# SCH_WasserQualliSensor_V1_1_2022-12-06.net
KiCad netlist of a schematic drawn in EasyEDA
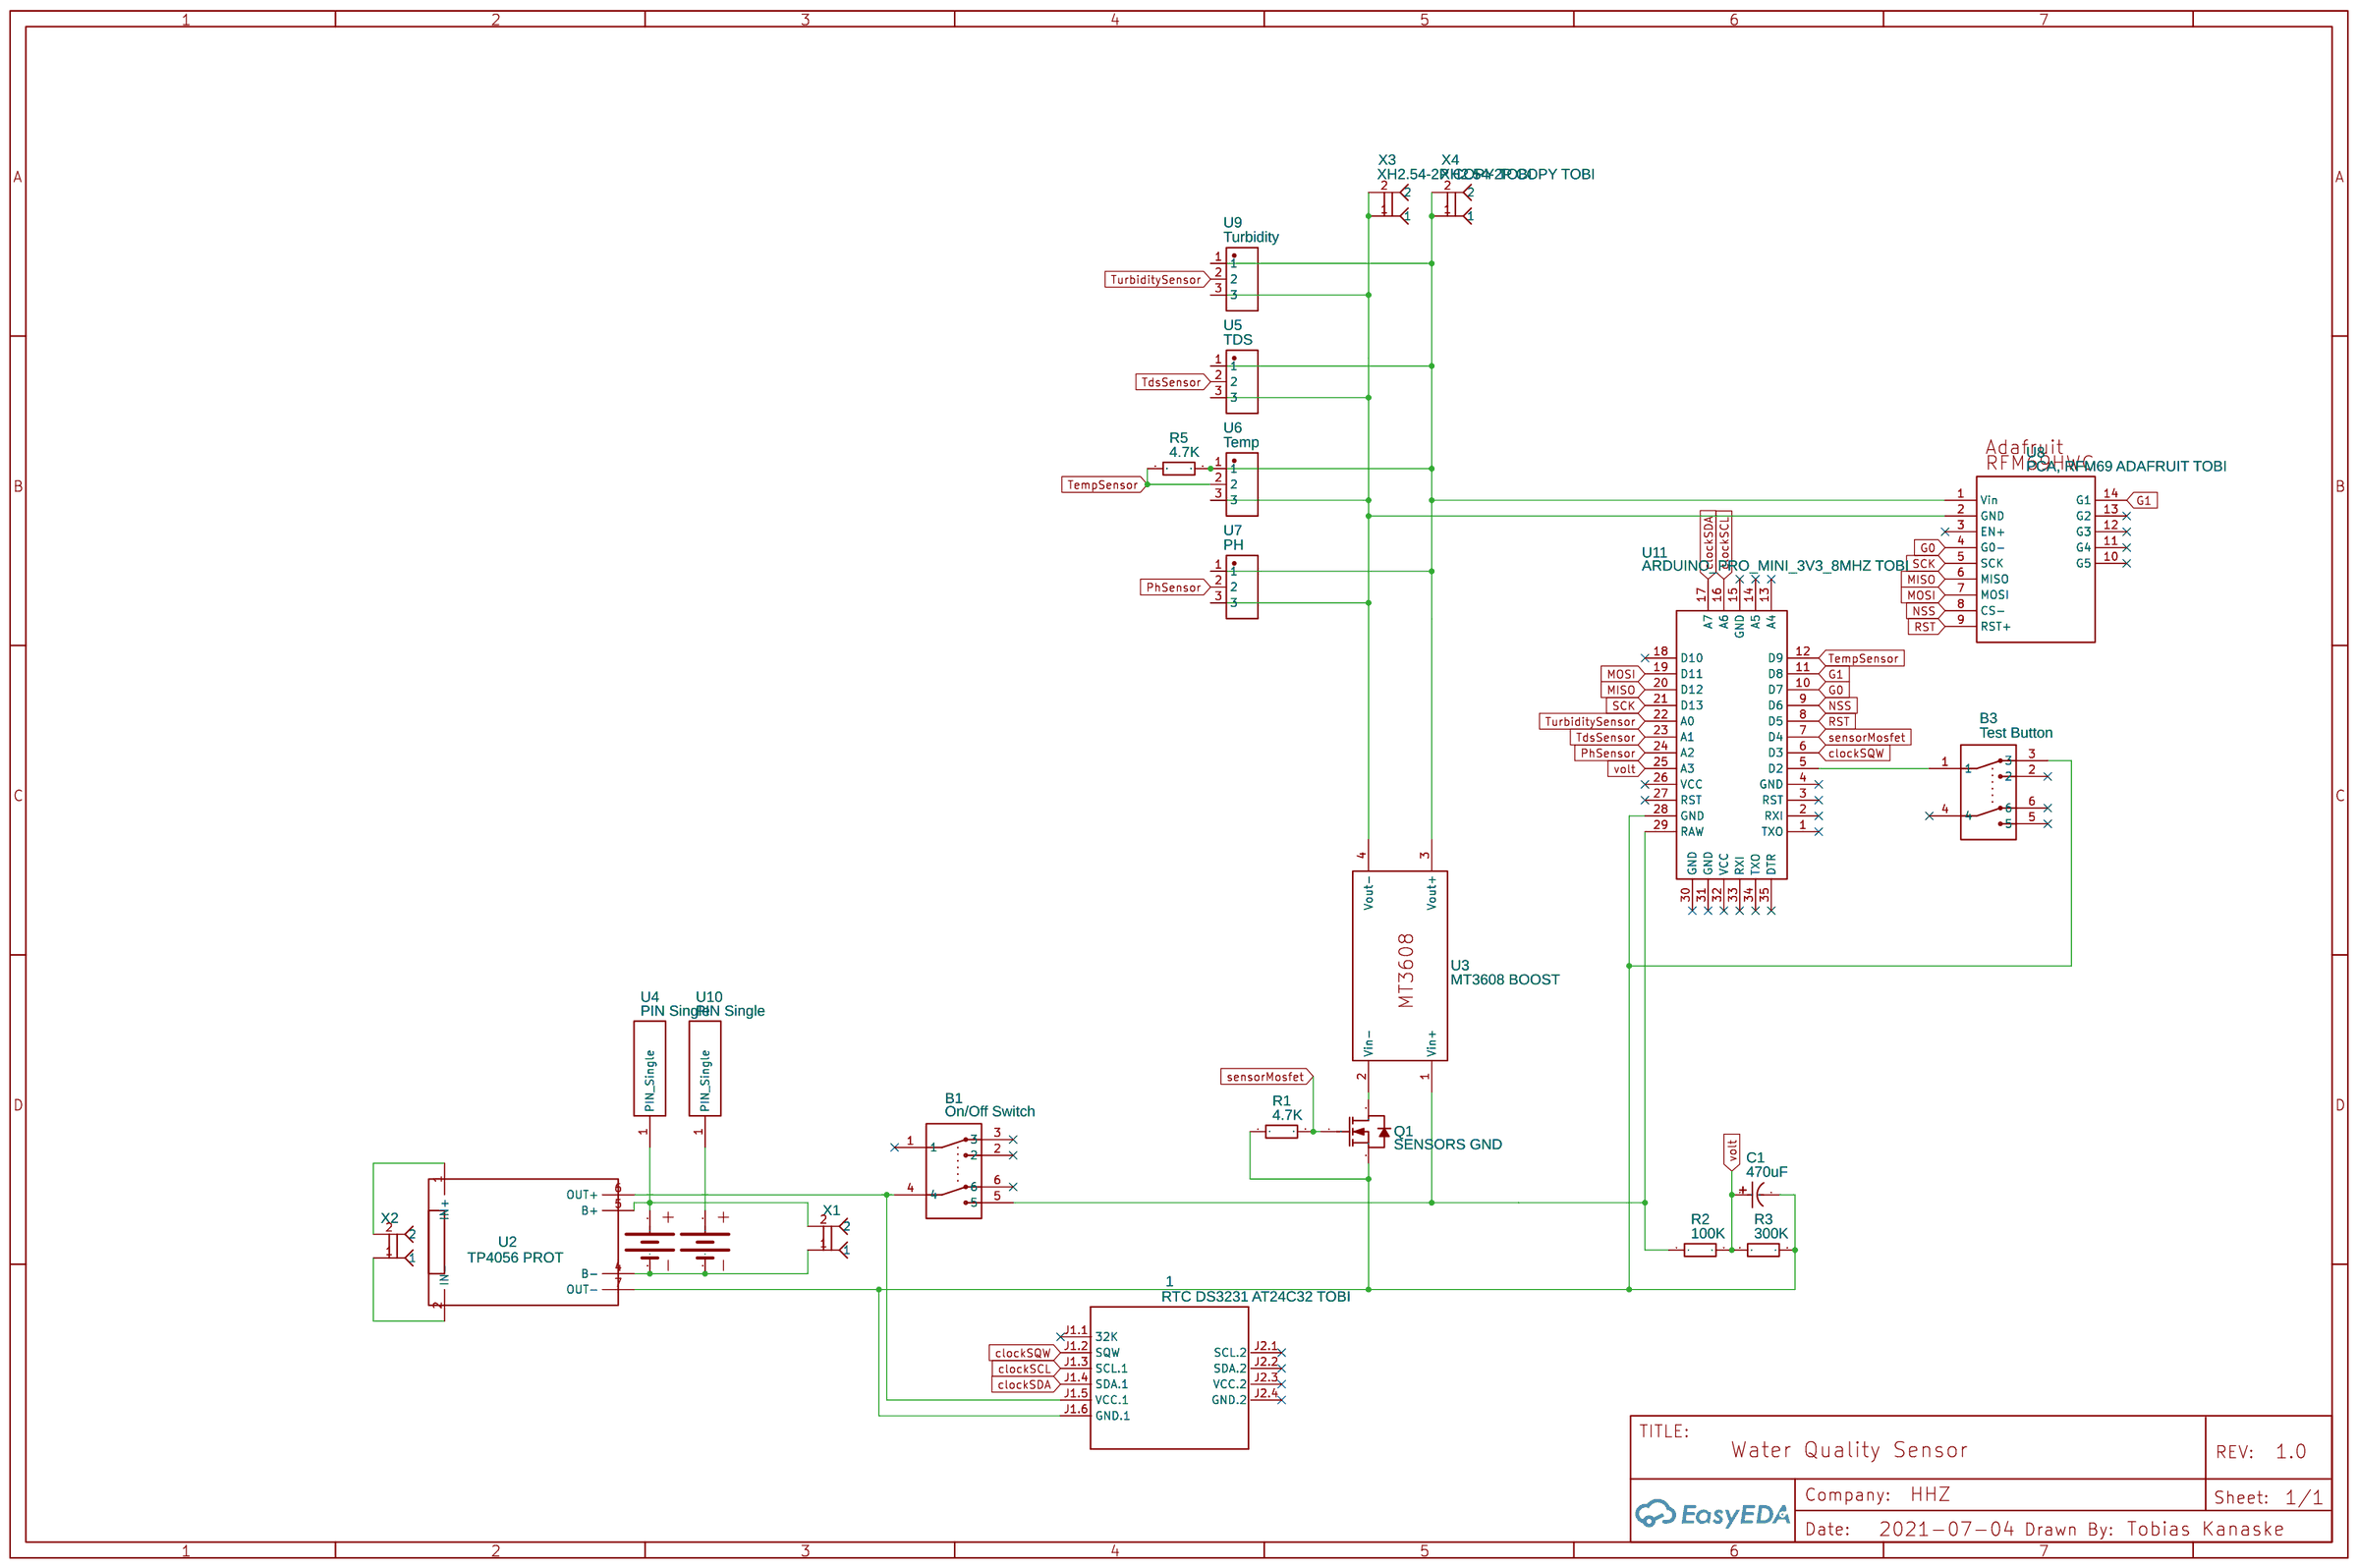
[diagram p0: schematic sheet]

(export (version "E")
  (design (tool "Eeschema 10.0.6"))
  (components
    (comp (ref "1") (value "RTC DS3231 AT24C32 TOBI") (libsource (lib "") (part "RTC DS3231 AT24C32 TOBI")))
    (comp (ref "3.1V") (value "18650") (libsource (lib "") (part "18650 SMD HOLDER 1S")))
    (comp (ref "4.2V") (value "18650") (libsource (lib "") (part "18650 SMD HOLDER 1S_1")))
    (comp (ref "B1")
      (value "On/Off Switch")
      (libsource (lib "") (part "LATCHING SWITCH BUTTON 8*8 6 PIN TOBI"))
    )
    (comp (ref "B3")
      (value "Test Button")
      (libsource (lib "") (part "LATCHING SWITCH BUTTON 8*8 6 PIN TOBI"))
    )
    (comp (ref "C1")
      (value "470uF")
      (fields
        (field (name "BOM_Manufacturer Part") "470uF 16V 6.3*12")
        (field (name "BOM_Supplier Part") "C43809")
      )
      (libsource (lib "") (part "KAPACITOR 470UF 16V 6.3*12 TOBI"))
    )
    (comp (ref "Q1")
      (value "SENSORS GND")
      (fields (field (name "BOM_Manufacturer Part") "IRLZ44NPBF") (field (name "BOM_Supplier Part") "C38774"))
      (libsource (lib "") (part "NPN MOSFET IRLZ44NPBF TOBI"))
    )
    (comp (ref "R1")
      (value "4.7K")
      (fields (field (name "BOM_Supplier Part") "C119339"))
      (libsource (lib "") (part "RESISTOR TOBI_1"))
    )
    (comp (ref "R2")
      (value "100K")
      (fields (field (name "BOM_Supplier Part") "C119339"))
      (libsource (lib "") (part "RESISTOR TOBI_1"))
    )
    (comp (ref "R3")
      (value "300K")
      (fields (field (name "BOM_Supplier Part") "C119339"))
      (libsource (lib "") (part "RESISTOR TOBI_1"))
    )
    (comp (ref "R5")
      (value "4.7K")
      (fields (field (name "BOM_Supplier Part") "C119339"))
      (libsource (lib "") (part "RESISTOR TOBI"))
    )
    (comp (ref "U2")
      (value "TP4056 PROT")
      (fields (field (name "BOM_Manufacturer Part") "TP4056-protect"))
      (libsource (lib "") (part "TP4056 PROT TOBI"))
    )
    (comp (ref "U3") (value "MT3608 BOOST") (libsource (lib "") (part "MT3608 BOOST TOBI")))
    (comp (ref "U4") (value "PIN Single") (libsource (lib "") (part "PIN Single")))
    (comp (ref "U5")
      (value "TDS")
      (fields
        (field (name "BOM_Manufacturer Part") "XH_2.54_3P")
        (field (name "BOM_Supplier Part") "C9900004241")
      )
      (libsource (lib "") (part "XH_2.54_3P TOBI"))
    )
    (comp (ref "U6")
      (value "Temp")
      (fields
        (field (name "BOM_Manufacturer Part") "XH_2.54_3P")
        (field (name "BOM_Supplier Part") "C9900004241")
      )
      (libsource (lib "") (part "XH_2.54_3P TOBI"))
    )
    (comp (ref "U7")
      (value "PH")
      (fields
        (field (name "BOM_Manufacturer Part") "XH_2.54_3P")
        (field (name "BOM_Supplier Part") "C9900004241")
      )
      (libsource (lib "") (part "XH_2.54_3P TOBI"))
    )
    (comp (ref "U8")
      (value "PCA, RFM69 ADAFRUIT TOBI")
      (fields (field (name "BOM_Manufacturer Part") "RFM69HCW") (field (name "BOM_Supplier Part") "C4746"))
      (libsource (lib "") (part "PCA, RFM69 ADAFRUIT TOBI"))
    )
    (comp (ref "U9")
      (value "Turbidity")
      (fields
        (field (name "BOM_Manufacturer Part") "XH_2.54_3P")
        (field (name "BOM_Supplier Part") "C9900004241")
      )
      (libsource (lib "") (part "XH_2.54_3P TOBI"))
    )
    (comp (ref "U10") (value "PIN Single") (libsource (lib "") (part "PIN Single")))
    (comp (ref "U11")
      (value "ARDUINO_PRO_MINI_3V3_8MHZ TOBI")
      (fields (field (name "BOM_Manufacturer Part") "Arduino_Pro_Mini_3V3_8Mhz"))
      (libsource (lib "") (part "ARDUINO_PRO_MINI_3V3_8MHZ TOBI"))
    )
    (comp (ref "X1") (value "XH2.54-2P") (libsource (lib "") (part "XH2.54-2P COPY TOBI")))
    (comp (ref "X2") (value "XH2.54-2P") (libsource (lib "") (part "XH2.54-2P COPY TOBI")))
    (comp (ref "X3")
      (value "XH2.54-2P COPY TOBI")
      (fields (field (name "BOM_Manufacturer Part") "XH2.54-2P"))
      (libsource (lib "") (part "XH2.54-2P COPY TOBI"))
    )
    (comp (ref "X4")
      (value "XH2.54-2P COPY TOBI")
      (fields (field (name "BOM_Manufacturer Part") "XH2.54-2P"))
      (libsource (lib "") (part "XH2.54-2P COPY TOBI"))
    )
  )
  (nets
    (net (code "1") (name "G0") (class "Default")
      (node (ref "U11") (pin "10") (pinfunction "D7_10") (pintype "unspecified"))
      (node (ref "U8") (pin "4") (pinfunction "G0-_4") (pintype "unspecified"))
    )
    (net (code "2") (name "G1") (class "Default")
      (node (ref "U11") (pin "11") (pinfunction "D8_11") (pintype "unspecified"))
      (node (ref "U8") (pin "14") (pinfunction "G1_14") (pintype "unspecified"))
    )
    (net (code "3") (name "MISO") (class "Default")
      (node (ref "U11") (pin "20") (pinfunction "D12_20") (pintype "unspecified"))
      (node (ref "U8") (pin "6") (pinfunction "MISO_6") (pintype "unspecified"))
    )
    (net (code "4") (name "MOSI") (class "Default")
      (node (ref "U11") (pin "19") (pinfunction "D11_19") (pintype "unspecified"))
      (node (ref "U8") (pin "7") (pinfunction "MOSI_7") (pintype "unspecified"))
    )
    (net (code "5") (name "NSS") (class "Default")
      (node (ref "U11") (pin "9") (pinfunction "D6_9") (pintype "unspecified"))
      (node (ref "U8") (pin "8") (pinfunction "CS-_8") (pintype "unspecified"))
    )
    (net (code "6") (name "Net-(1-GND.1)") (class "Default")
      (node (ref "1") (pin "J1.6") (pinfunction "GND.1_J1.6") (pintype "bidirectional"))
      (node (ref "B3") (pin "3") (pinfunction "3_3") (pintype "unspecified"))
      (node (ref "C1") (pin "2") (pinfunction "2_2") (pintype "input"))
      (node (ref "Q1") (pin "3") (pinfunction "S_3") (pintype "unspecified"))
      (node (ref "R1") (pin "1") (pinfunction "1_1") (pintype "unspecified"))
      (node (ref "R3") (pin "2") (pinfunction "2_2") (pintype "unspecified"))
      (node (ref "U11") (pin "28") (pinfunction "GND_28") (pintype "unspecified"))
      (node (ref "U2") (pin "7") (pinfunction "OUT-_7") (pintype "unspecified"))
    )
    (net (code "7") (name "Net-(1-VCC.1)") (class "Default")
      (node (ref "1") (pin "J1.5") (pinfunction "VCC.1_J1.5") (pintype "bidirectional"))
      (node (ref "B1") (pin "4") (pinfunction "4_4") (pintype "unspecified"))
      (node (ref "U2") (pin "6") (pinfunction "OUT+_6") (pintype "unspecified"))
    )
    (net (code "8") (name "Net-(3.1V-+)") (class "Default")
      (node (ref "3.1V") (pin "1") (pinfunction "+_1") (pintype "passive"))
      (node (ref "U10") (pin "1") (pinfunction "PIN_Single_1") (pintype "unspecified"))
    )
    (net (code "9") (name "Net-(3.1V--)") (class "Default")
      (node (ref "3.1V") (pin "2") (pinfunction "-_2") (pintype "passive"))
      (node (ref "4.2V") (pin "2") (pinfunction "-_2") (pintype "passive"))
      (node (ref "U2") (pin "4") (pinfunction "B-_4") (pintype "unspecified"))
      (node (ref "X1") (pin "1") (pinfunction "1_1") (pintype "unspecified"))
    )
    (net (code "10") (name "Net-(4.2V-+)") (class "Default")
      (node (ref "4.2V") (pin "1") (pinfunction "+_1") (pintype "passive"))
      (node (ref "U2") (pin "5") (pinfunction "B+_5") (pintype "unspecified"))
      (node (ref "U4") (pin "1") (pinfunction "PIN_Single_1") (pintype "unspecified"))
      (node (ref "X1") (pin "2") (pinfunction "2_2") (pintype "unspecified"))
    )
    (net (code "11") (name "Net-(Q1-D)") (class "Default")
      (node (ref "Q1") (pin "2") (pinfunction "D_2") (pintype "unspecified"))
      (node (ref "U3") (pin "2") (pinfunction "Vin-_2") (pintype "unspecified"))
    )
    (net (code "12") (name "Net-(U2-IN+)") (class "Default")
      (node (ref "U2") (pin "1") (pinfunction "IN+_1") (pintype "unspecified"))
      (node (ref "X2") (pin "2") (pinfunction "2_2") (pintype "unspecified"))
    )
    (net (code "13") (name "Net-(U2-IN-)") (class "Default")
      (node (ref "U2") (pin "2") (pinfunction "IN-_2") (pintype "unspecified"))
      (node (ref "X2") (pin "1") (pinfunction "1_1") (pintype "unspecified"))
    )
    (net (code "14") (name "Net-(U3-Vout+)") (class "Default")
      (node (ref "R5") (pin "1") (pinfunction "1_1") (pintype "unspecified"))
      (node (ref "U3") (pin "3") (pinfunction "Vout+_3") (pintype "unspecified"))
      (node (ref "U5") (pin "1") (pinfunction "1_1") (pintype "unspecified"))
      (node (ref "U6") (pin "1") (pinfunction "1_1") (pintype "unspecified"))
      (node (ref "U7") (pin "1") (pinfunction "1_1") (pintype "unspecified"))
      (node (ref "U8") (pin "1") (pinfunction "Vin_1") (pintype "unspecified"))
      (node (ref "U9") (pin "1") (pinfunction "1_1") (pintype "unspecified"))
      (node (ref "X4") (pin "1") (pinfunction "1_1") (pintype "unspecified"))
      (node (ref "X4") (pin "2") (pinfunction "2_2") (pintype "unspecified"))
    )
    (net (code "15") (name "Net-(U3-Vout-)") (class "Default")
      (node (ref "U3") (pin "4") (pinfunction "Vout-_4") (pintype "unspecified"))
      (node (ref "U5") (pin "3") (pinfunction "3_3") (pintype "unspecified"))
      (node (ref "U6") (pin "3") (pinfunction "3_3") (pintype "unspecified"))
      (node (ref "U7") (pin "3") (pinfunction "3_3") (pintype "unspecified"))
      (node (ref "U8") (pin "2") (pinfunction "GND_2") (pintype "unspecified"))
      (node (ref "U9") (pin "3") (pinfunction "3_3") (pintype "unspecified"))
      (node (ref "X3") (pin "1") (pinfunction "1_1") (pintype "unspecified"))
      (node (ref "X3") (pin "2") (pinfunction "2_2") (pintype "unspecified"))
    )
    (net (code "16") (name "Net-(U11-D2)") (class "Default")
      (node (ref "B3") (pin "1") (pinfunction "1_1") (pintype "unspecified"))
      (node (ref "U11") (pin "5") (pinfunction "D2_5") (pintype "unspecified"))
    )
    (net (code "17") (name "Net-(U11-RAW)") (class "Default")
      (node (ref "B1") (pin "5") (pinfunction "5_5") (pintype "unspecified"))
      (node (ref "R2") (pin "1") (pinfunction "1_1") (pintype "unspecified"))
      (node (ref "U11") (pin "29") (pinfunction "RAW_29") (pintype "unspecified"))
      (node (ref "U3") (pin "1") (pinfunction "Vin+_1") (pintype "unspecified"))
    )
    (net (code "18") (name "PhSensor") (class "Default")
      (node (ref "U11") (pin "24") (pinfunction "A2_24") (pintype "unspecified"))
      (node (ref "U7") (pin "2") (pinfunction "2_2") (pintype "unspecified"))
    )
    (net (code "19") (name "RST") (class "Default")
      (node (ref "U11") (pin "8") (pinfunction "D5_8") (pintype "unspecified"))
      (node (ref "U8") (pin "9") (pinfunction "RST+_9") (pintype "unspecified"))
    )
    (net (code "20") (name "SCK") (class "Default")
      (node (ref "U11") (pin "21") (pinfunction "D13_21") (pintype "unspecified"))
      (node (ref "U8") (pin "5") (pinfunction "SCK_5") (pintype "unspecified"))
    )
    (net (code "21") (name "TdsSensor") (class "Default")
      (node (ref "U11") (pin "23") (pinfunction "A1_23") (pintype "unspecified"))
      (node (ref "U5") (pin "2") (pinfunction "2_2") (pintype "unspecified"))
    )
    (net (code "22") (name "TempSensor") (class "Default")
      (node (ref "R5") (pin "2") (pinfunction "2_2") (pintype "unspecified"))
      (node (ref "U11") (pin "12") (pinfunction "D9_12") (pintype "unspecified"))
      (node (ref "U6") (pin "2") (pinfunction "2_2") (pintype "unspecified"))
    )
    (net (code "23") (name "TurbiditySensor") (class "Default")
      (node (ref "U11") (pin "22") (pinfunction "A0_22") (pintype "unspecified"))
      (node (ref "U9") (pin "2") (pinfunction "2_2") (pintype "unspecified"))
    )
    (net (code "24") (name "clockSCL") (class "Default")
      (node (ref "1") (pin "J1.3") (pinfunction "SCL.1_J1.3") (pintype "bidirectional"))
      (node (ref "U11") (pin "16") (pinfunction "A6_16") (pintype "unspecified"))
    )
    (net (code "25") (name "clockSDA") (class "Default")
      (node (ref "1") (pin "J1.4") (pinfunction "SDA.1_J1.4") (pintype "bidirectional"))
      (node (ref "U11") (pin "17") (pinfunction "A7_17") (pintype "unspecified"))
    )
    (net (code "26") (name "clockSQW") (class "Default")
      (node (ref "1") (pin "J1.2") (pinfunction "SQW_J1.2") (pintype "bidirectional"))
      (node (ref "U11") (pin "6") (pinfunction "D3_6") (pintype "unspecified"))
    )
    (net (code "27") (name "sensorMosfet") (class "Default")
      (node (ref "Q1") (pin "1") (pinfunction "G_1") (pintype "unspecified"))
      (node (ref "R1") (pin "2") (pinfunction "2_2") (pintype "unspecified"))
      (node (ref "U11") (pin "7") (pinfunction "D4_7") (pintype "unspecified"))
    )
    (net (code "28") (name "unconnected-(1-32K-PadJ1.1)") (class "Default")
      (node (ref "1") (pin "J1.1") (pinfunction "32K_J1.1") (pintype "bidirectional+no_connect"))
    )
    (net (code "29") (name "unconnected-(1-GND.2-PadJ2.4)") (class "Default")
      (node (ref "1") (pin "J2.4") (pinfunction "GND.2_J2.4") (pintype "bidirectional+no_connect"))
    )
    (net (code "30") (name "unconnected-(1-SCL.2-PadJ2.1)") (class "Default")
      (node (ref "1") (pin "J2.1") (pinfunction "SCL.2_J2.1") (pintype "bidirectional+no_connect"))
    )
    (net (code "31") (name "unconnected-(1-SDA.2-PadJ2.2)") (class "Default")
      (node (ref "1") (pin "J2.2") (pinfunction "SDA.2_J2.2") (pintype "bidirectional+no_connect"))
    )
    (net (code "32") (name "unconnected-(1-VCC.2-PadJ2.3)") (class "Default")
      (node (ref "1") (pin "J2.3") (pinfunction "VCC.2_J2.3") (pintype "bidirectional+no_connect"))
    )
    (net (code "33") (name "unconnected-(B1-Pad1)") (class "Default")
      (node (ref "B1") (pin "1") (pinfunction "1_1") (pintype "unspecified+no_connect"))
    )
    (net (code "34") (name "unconnected-(B1-Pad2)") (class "Default")
      (node (ref "B1") (pin "2") (pinfunction "2_2") (pintype "unspecified+no_connect"))
    )
    (net (code "35") (name "unconnected-(B1-Pad3)") (class "Default")
      (node (ref "B1") (pin "3") (pinfunction "3_3") (pintype "unspecified+no_connect"))
    )
    (net (code "36") (name "unconnected-(B1-Pad6)") (class "Default")
      (node (ref "B1") (pin "6") (pinfunction "6_6") (pintype "unspecified+no_connect"))
    )
    (net (code "37") (name "unconnected-(B3-Pad2)") (class "Default")
      (node (ref "B3") (pin "2") (pinfunction "2_2") (pintype "unspecified+no_connect"))
    )
    (net (code "38") (name "unconnected-(B3-Pad4)") (class "Default")
      (node (ref "B3") (pin "4") (pinfunction "4_4") (pintype "unspecified+no_connect"))
    )
    (net (code "39") (name "unconnected-(B3-Pad5)") (class "Default")
      (node (ref "B3") (pin "5") (pinfunction "5_5") (pintype "unspecified+no_connect"))
    )
    (net (code "40") (name "unconnected-(B3-Pad6)") (class "Default")
      (node (ref "B3") (pin "6") (pinfunction "6_6") (pintype "unspecified+no_connect"))
    )
    (net (code "41") (name "unconnected-(U8-EN+-Pad3)") (class "Default")
      (node (ref "U8") (pin "3") (pinfunction "EN+_3") (pintype "unspecified+no_connect"))
    )
    (net (code "42") (name "unconnected-(U8-G2-Pad13)") (class "Default")
      (node (ref "U8") (pin "13") (pinfunction "G2_13") (pintype "unspecified+no_connect"))
    )
    (net (code "43") (name "unconnected-(U8-G3-Pad12)") (class "Default")
      (node (ref "U8") (pin "12") (pinfunction "G3_12") (pintype "unspecified+no_connect"))
    )
    (net (code "44") (name "unconnected-(U8-G4-Pad11)") (class "Default")
      (node (ref "U8") (pin "11") (pinfunction "G4_11") (pintype "unspecified+no_connect"))
    )
    (net (code "45") (name "unconnected-(U8-G5-Pad10)") (class "Default")
      (node (ref "U8") (pin "10") (pinfunction "G5_10") (pintype "unspecified+no_connect"))
    )
    (net (code "46") (name "unconnected-(U11-A4-Pad13)") (class "Default")
      (node (ref "U11") (pin "13") (pinfunction "A4_13") (pintype "unspecified+no_connect"))
    )
    (net (code "47") (name "unconnected-(U11-A5-Pad14)") (class "Default")
      (node (ref "U11") (pin "14") (pinfunction "A5_14") (pintype "unspecified+no_connect"))
    )
    (net (code "48") (name "unconnected-(U11-D10-Pad18)") (class "Default")
      (node (ref "U11") (pin "18") (pinfunction "D10_18") (pintype "unspecified+no_connect"))
    )
    (net (code "49") (name "unconnected-(U11-DTR-Pad35)") (class "Default")
      (node (ref "U11") (pin "35") (pinfunction "DTR_35") (pintype "unspecified+no_connect"))
    )
    (net (code "50") (name "unconnected-(U11-GND-Pad4)") (class "Default")
      (node (ref "U11") (pin "4") (pinfunction "GND_4") (pintype "unspecified+no_connect"))
    )
    (net (code "51") (name "unconnected-(U11-GND-Pad15)") (class "Default")
      (node (ref "U11") (pin "15") (pinfunction "GND_15") (pintype "unspecified+no_connect"))
    )
    (net (code "52") (name "unconnected-(U11-GND-Pad30)") (class "Default")
      (node (ref "U11") (pin "30") (pinfunction "GND_30") (pintype "unspecified+no_connect"))
    )
    (net (code "53") (name "unconnected-(U11-GND-Pad31)") (class "Default")
      (node (ref "U11") (pin "31") (pinfunction "GND_31") (pintype "unspecified+no_connect"))
    )
    (net (code "54") (name "unconnected-(U11-RST-Pad3)") (class "Default")
      (node (ref "U11") (pin "3") (pinfunction "RST_3") (pintype "unspecified+no_connect"))
    )
    (net (code "55") (name "unconnected-(U11-RST-Pad27)") (class "Default")
      (node (ref "U11") (pin "27") (pinfunction "RST_27") (pintype "unspecified+no_connect"))
    )
    (net (code "56") (name "unconnected-(U11-RXI-Pad2)") (class "Default")
      (node (ref "U11") (pin "2") (pinfunction "RXI_2") (pintype "unspecified+no_connect"))
    )
    (net (code "57") (name "unconnected-(U11-RXI-Pad33)") (class "Default")
      (node (ref "U11") (pin "33") (pinfunction "RXI_33") (pintype "unspecified+no_connect"))
    )
    (net (code "58") (name "unconnected-(U11-TXO-Pad1)") (class "Default")
      (node (ref "U11") (pin "1") (pinfunction "TXO_1") (pintype "unspecified+no_connect"))
    )
    (net (code "59") (name "unconnected-(U11-TXO-Pad34)") (class "Default")
      (node (ref "U11") (pin "34") (pinfunction "TXO_34") (pintype "unspecified+no_connect"))
    )
    (net (code "60") (name "unconnected-(U11-VCC-Pad26)") (class "Default")
      (node (ref "U11") (pin "26") (pinfunction "VCC_26") (pintype "unspecified+no_connect"))
    )
    (net (code "61") (name "unconnected-(U11-VCC-Pad32)") (class "Default")
      (node (ref "U11") (pin "32") (pinfunction "VCC_32") (pintype "unspecified+no_connect"))
    )
    (net (code "62") (name "volt") (class "Default")
      (node (ref "C1") (pin "1") (pinfunction "1_1") (pintype "input"))
      (node (ref "R2") (pin "2") (pinfunction "2_2") (pintype "unspecified"))
      (node (ref "R3") (pin "1") (pinfunction "1_1") (pintype "unspecified"))
      (node (ref "U11") (pin "25") (pinfunction "A3_25") (pintype "unspecified"))
    )
  )
)
